# SilentStepStick-TMC2100_v12_5V.net
KiCad netlist of a schematic drawn in EAGLE
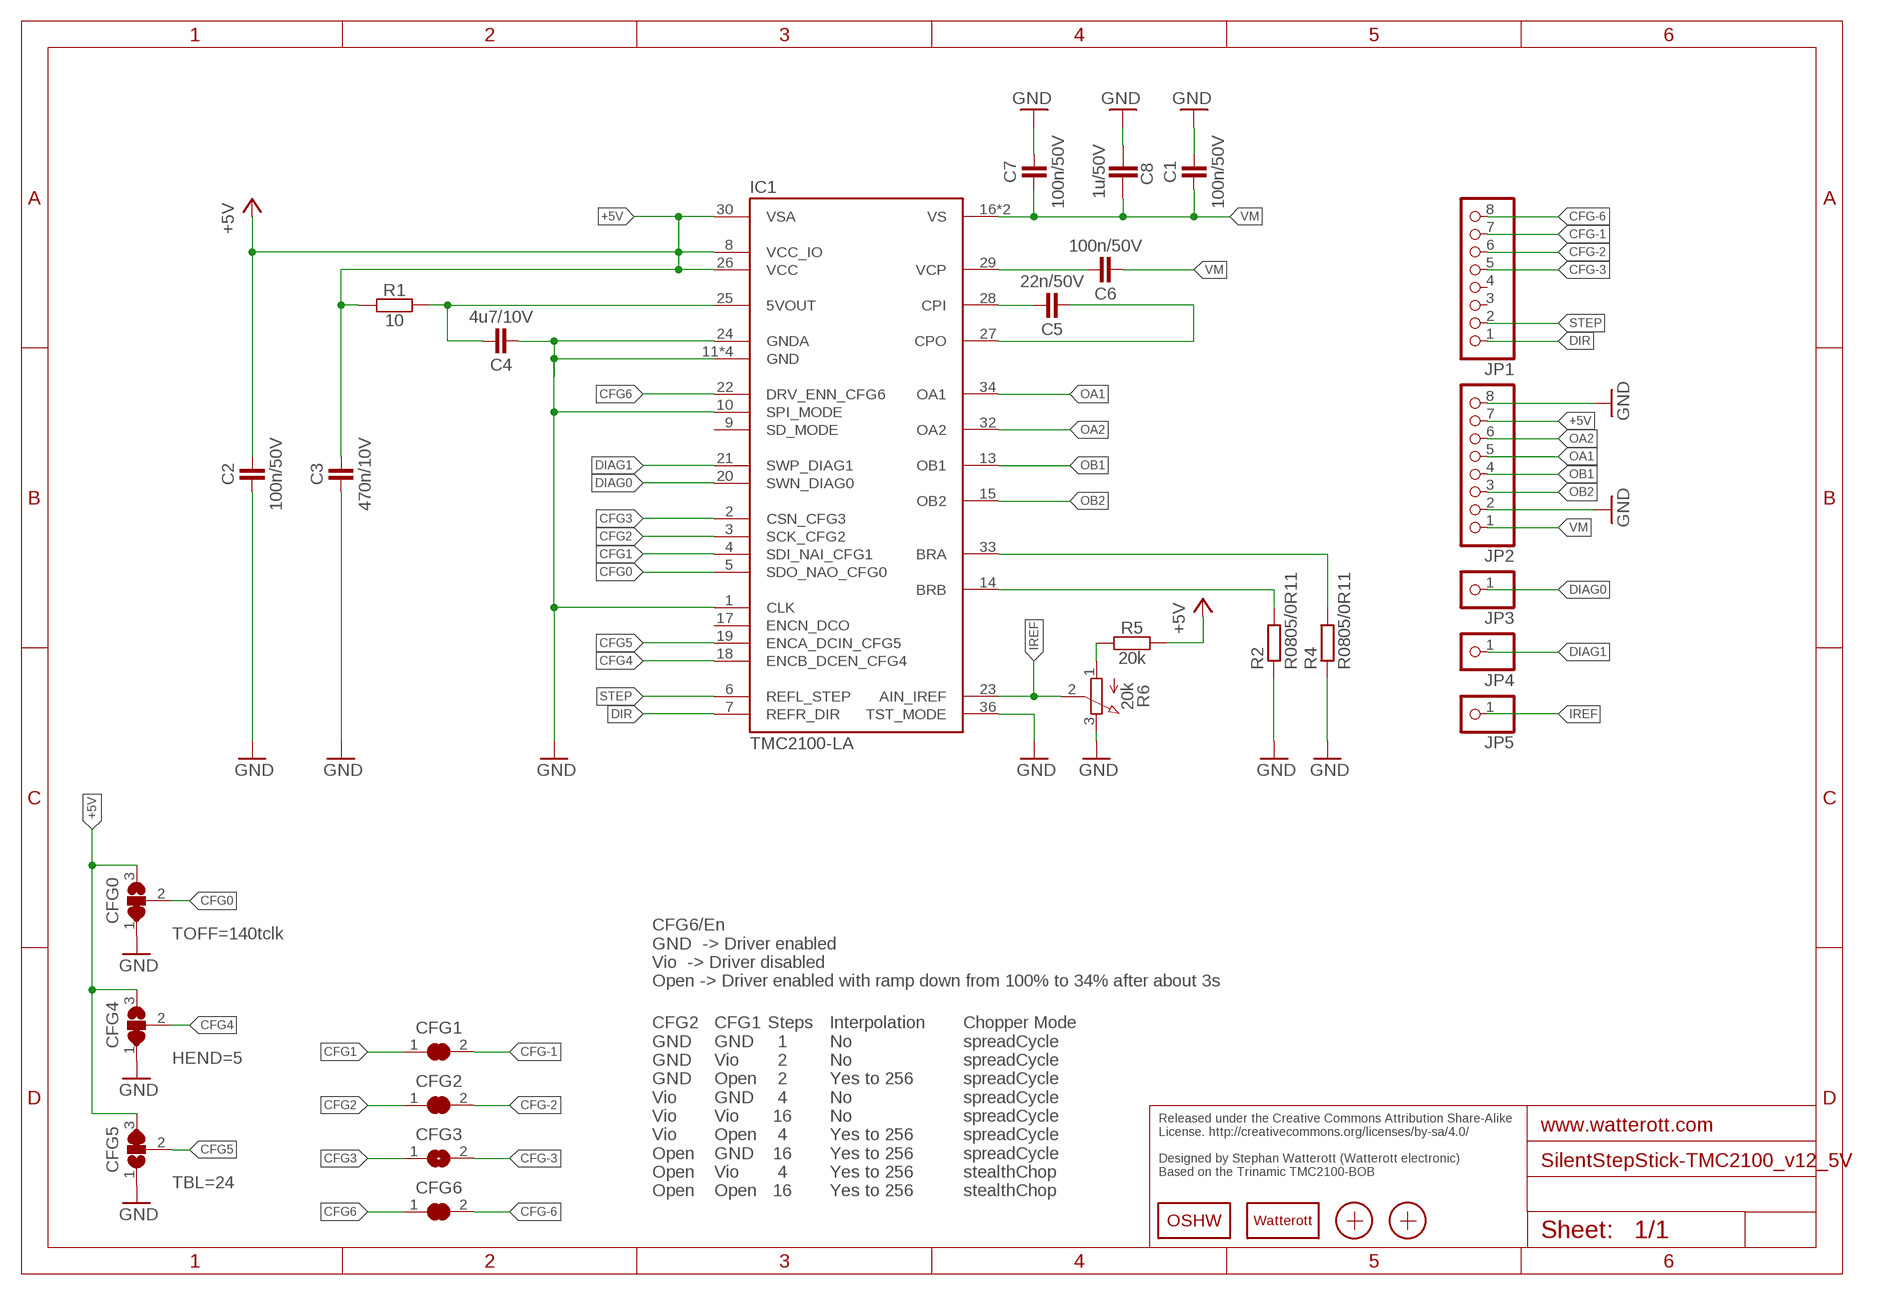
[diagram p0: schematic, sheet 1]

(export (version "E")
  (design (tool "Eeschema 10.0.6"))
  (components
    (comp (ref "C1")
      (value "100n/50V")
      (footprint "eagle-import:C0402")
      (libsource (lib "eagle-import") (part "CAPACITOR-0402"))
    )
    (comp (ref "C2")
      (value "100n/50V")
      (footprint "eagle-import:C0402")
      (libsource (lib "eagle-import") (part "CAPACITOR-0402"))
    )
    (comp (ref "C3")
      (value "470n/10V")
      (footprint "eagle-import:C0402")
      (libsource (lib "eagle-import") (part "CAPACITOR-0402"))
    )
    (comp (ref "C4")
      (value "4u7/10V")
      (footprint "eagle-import:C0402")
      (libsource (lib "eagle-import") (part "CAPACITOR-0402"))
    )
    (comp (ref "C5")
      (value "22n/50V")
      (footprint "eagle-import:C0402")
      (libsource (lib "eagle-import") (part "CAPACITOR-0402"))
    )
    (comp (ref "C6")
      (value "100n/50V")
      (footprint "eagle-import:C0402")
      (libsource (lib "eagle-import") (part "CAPACITOR-0402"))
    )
    (comp (ref "C7")
      (value "100n/50V")
      (footprint "eagle-import:C0402")
      (libsource (lib "eagle-import") (part "CAPACITOR-0402"))
    )
    (comp (ref "C8")
      (value "1u/50V")
      (footprint "eagle-import:C0603")
      (libsource (lib "eagle-import") (part "C-EUC0603"))
    )
    (comp (ref "CFG0")
      (value "JUMPER3-0201")
      (footprint "eagle-import:JUMPER3-0201")
      (libsource (lib "eagle-import") (part "JUMPER3-0201"))
    )
    (comp (ref "CFG1")
      (value "JUMPER2-0201")
      (footprint "eagle-import:JUMPER2-0201")
      (libsource (lib "eagle-import") (part "JUMPER2-0201"))
    )
    (comp (ref "CFG2")
      (value "JUMPER2-0201")
      (footprint "eagle-import:JUMPER2-0201")
      (libsource (lib "eagle-import") (part "JUMPER2-0201"))
    )
    (comp (ref "CFG3")
      (value "JUMPER2-0201")
      (footprint "eagle-import:JUMPER2-0201")
      (libsource (lib "eagle-import") (part "JUMPER2-0201"))
    )
    (comp (ref "CFG4")
      (value "JUMPER3-0201")
      (footprint "eagle-import:JUMPER3-0201")
      (libsource (lib "eagle-import") (part "JUMPER3-0201"))
    )
    (comp (ref "CFG5")
      (value "JUMPER3-0201")
      (footprint "eagle-import:JUMPER3-0201")
      (libsource (lib "eagle-import") (part "JUMPER3-0201"))
    )
    (comp (ref "CFG6")
      (value "JUMPER2-0201")
      (footprint "eagle-import:JUMPER2-0201")
      (libsource (lib "eagle-import") (part "JUMPER2-0201"))
    )
    (comp (ref "IC1")
      (value "TMC2100-LA")
      (footprint "eagle-import:QFN36-PAD")
      (libsource (lib "eagle-import") (part "TMC21X0-LA"))
    )
    (comp (ref "JP1")
      (value "PINHD-1X08_2.54-S")
      (footprint "eagle-import:1X08-S")
      (libsource (lib "eagle-import") (part "PINHD-1X08_2.54-S"))
    )
    (comp (ref "JP2")
      (value "PINHD-1X08_2.54-S")
      (footprint "eagle-import:1X08-S")
      (libsource (lib "eagle-import") (part "PINHD-1X08_2.54-S"))
    )
    (comp (ref "JP3")
      (value "PINHD-1X1")
      (footprint "eagle-import:1X01")
      (libsource (lib "eagle-import") (part "PINHD-1X1"))
    )
    (comp (ref "JP4")
      (value "PINHD-1X1")
      (footprint "eagle-import:1X01")
      (libsource (lib "eagle-import") (part "PINHD-1X1"))
    )
    (comp (ref "JP5")
      (value "PINHD-1X1")
      (footprint "eagle-import:1X01")
      (libsource (lib "eagle-import") (part "PINHD-1X1"))
    )
    (comp (ref "LOGO1")
      (value "OSHW_LOGOX0070")
      (footprint "eagle-import:OSHW_6X70")
      (libsource (lib "eagle-import") (part "OSHW_LOGOX0070"))
    )
    (comp (ref "LOGO2")
      (value "LOGO-S_PLACE_M")
      (footprint "eagle-import:SPARK_TPLACE_M")
      (libsource (lib "eagle-import") (part "LOGO-S_PLACE_M"))
    )
    (comp (ref "R1")
      (value "10")
      (footprint "eagle-import:C0402")
      (libsource (lib "eagle-import") (part "RESISTOR-0402"))
    )
    (comp (ref "R2")
      (value "R0805/0R11")
      (footprint "eagle-import:M0805")
      (libsource (lib "eagle-import") (part "R-EU_M0805"))
    )
    (comp (ref "R4")
      (value "R0805/0R11")
      (footprint "eagle-import:M0805")
      (libsource (lib "eagle-import") (part "R-EU_M0805"))
    )
    (comp (ref "R5")
      (value "20k")
      (footprint "eagle-import:C0402")
      (libsource (lib "eagle-import") (part "RESISTOR-0402"))
    )
    (comp (ref "R6")
      (value "20k")
      (footprint "eagle-import:POT_EVM3R")
      (libsource (lib "eagle-import") (part "POTEVM3R"))
    )
    (comp (ref "X1")
      (value "PASSER-07")
      (footprint "eagle-import:PASSER_07MM")
      (libsource (lib "eagle-import") (part "PASSER-07"))
    )
    (comp (ref "X2")
      (value "PASSER-07")
      (footprint "eagle-import:PASSER_07MM")
      (libsource (lib "eagle-import") (part "PASSER-07"))
    )
  )
  (nets
    (net (code "1") (name "+5V") (class "Default")
      (node (ref "C2") (pin "2") (pinfunction "2_2") (pintype "passive"))
      (node (ref "C3") (pin "2") (pinfunction "2_2") (pintype "passive"))
      (node (ref "CFG0") (pin "3") (pinfunction "3_3") (pintype "passive"))
      (node (ref "CFG4") (pin "3") (pinfunction "3_3") (pintype "passive"))
      (node (ref "CFG5") (pin "3") (pinfunction "3_3") (pintype "passive"))
      (node (ref "IC1") (pin "26") (pinfunction "VCC_26") (pintype "power_in"))
      (node (ref "IC1") (pin "30") (pinfunction "VSA_30") (pintype "power_in"))
      (node (ref "IC1") (pin "8") (pinfunction "VCC_IO_8") (pintype "power_in"))
      (node (ref "JP2") (pin "7") (pinfunction "7_7") (pintype "passive"))
      (node (ref "R1") (pin "1") (pinfunction "1_1") (pintype "passive"))
      (node (ref "R5") (pin "2") (pinfunction "2_2") (pintype "passive"))
    )
    (net (code "2") (name "CFG-1") (class "Default")
      (node (ref "CFG1") (pin "2") (pinfunction "2_2") (pintype "passive"))
      (node (ref "JP1") (pin "7") (pinfunction "7_7") (pintype "passive"))
    )
    (net (code "3") (name "CFG-2") (class "Default")
      (node (ref "CFG2") (pin "2") (pinfunction "2_2") (pintype "passive"))
      (node (ref "JP1") (pin "6") (pinfunction "6_6") (pintype "passive"))
    )
    (net (code "4") (name "CFG-3") (class "Default")
      (node (ref "CFG3") (pin "2") (pinfunction "2_2") (pintype "passive"))
      (node (ref "JP1") (pin "5") (pinfunction "5_5") (pintype "passive"))
    )
    (net (code "5") (name "CFG-6") (class "Default")
      (node (ref "CFG6") (pin "2") (pinfunction "2_2") (pintype "passive"))
      (node (ref "JP1") (pin "8") (pinfunction "8_8") (pintype "passive"))
    )
    (net (code "6") (name "CFG0") (class "Default")
      (node (ref "CFG0") (pin "2") (pinfunction "2_2") (pintype "passive"))
      (node (ref "IC1") (pin "5") (pinfunction "SDO_NAO_CFG0_5") (pintype "bidirectional"))
    )
    (net (code "7") (name "CFG1") (class "Default")
      (node (ref "CFG1") (pin "1") (pinfunction "1_1") (pintype "passive"))
      (node (ref "IC1") (pin "4") (pinfunction "SDI_NAI_CFG1_4") (pintype "bidirectional"))
    )
    (net (code "8") (name "CFG2") (class "Default")
      (node (ref "CFG2") (pin "1") (pinfunction "1_1") (pintype "passive"))
      (node (ref "IC1") (pin "3") (pinfunction "SCK_CFG2_3") (pintype "bidirectional"))
    )
    (net (code "9") (name "CFG3") (class "Default")
      (node (ref "CFG3") (pin "1") (pinfunction "1_1") (pintype "passive"))
      (node (ref "IC1") (pin "2") (pinfunction "CSN_CFG3_2") (pintype "bidirectional"))
    )
    (net (code "10") (name "CFG4") (class "Default")
      (node (ref "CFG4") (pin "2") (pinfunction "2_2") (pintype "passive"))
      (node (ref "IC1") (pin "18") (pinfunction "ENCB_DCEN_CFG4_18") (pintype "bidirectional"))
    )
    (net (code "11") (name "CFG5") (class "Default")
      (node (ref "CFG5") (pin "2") (pinfunction "2_2") (pintype "passive"))
      (node (ref "IC1") (pin "19") (pinfunction "ENCA_DCIN_CFG5_19") (pintype "bidirectional"))
    )
    (net (code "12") (name "CFG6") (class "Default")
      (node (ref "CFG6") (pin "1") (pinfunction "1_1") (pintype "passive"))
      (node (ref "IC1") (pin "22") (pinfunction "DRV_ENN_CFG6_22") (pintype "bidirectional"))
    )
    (net (code "13") (name "DIAG0") (class "Default")
      (node (ref "IC1") (pin "20") (pinfunction "SWN_DIAG0_20") (pintype "bidirectional"))
      (node (ref "JP3") (pin "1") (pinfunction "1_1") (pintype "passive"))
    )
    (net (code "14") (name "DIAG1") (class "Default")
      (node (ref "IC1") (pin "21") (pinfunction "SWP_DIAG1_21") (pintype "bidirectional"))
      (node (ref "JP4") (pin "1") (pinfunction "1_1") (pintype "passive"))
    )
    (net (code "15") (name "DIR") (class "Default")
      (node (ref "IC1") (pin "7") (pinfunction "REFR_DIR_7") (pintype "bidirectional"))
      (node (ref "JP1") (pin "1") (pinfunction "1_1") (pintype "passive"))
    )
    (net (code "16") (name "GND") (class "Default")
      (node (ref "C1") (pin "2") (pinfunction "2_2") (pintype "passive"))
      (node (ref "C2") (pin "1") (pinfunction "1_1") (pintype "passive"))
      (node (ref "C3") (pin "1") (pinfunction "1_1") (pintype "passive"))
      (node (ref "C4") (pin "1") (pinfunction "1_1") (pintype "passive"))
      (node (ref "C7") (pin "2") (pinfunction "2_2") (pintype "passive"))
      (node (ref "C8") (pin "2") (pinfunction "2_2") (pintype "passive"))
      (node (ref "CFG0") (pin "1") (pinfunction "1_1") (pintype "passive"))
      (node (ref "CFG4") (pin "1") (pinfunction "1_1") (pintype "passive"))
      (node (ref "CFG5") (pin "1") (pinfunction "1_1") (pintype "passive"))
      (node (ref "IC1") (pin "1") (pinfunction "CLK_1") (pintype "bidirectional"))
      (node (ref "IC1") (pin "10") (pinfunction "SPI_MODE_10") (pintype "bidirectional"))
      (node (ref "IC1") (pin "11") (pinfunction "GND_11") (pintype "power_in"))
      (node (ref "IC1") (pin "12") (pinfunction "GND_12") (pintype "power_in"))
      (node (ref "IC1") (pin "24") (pinfunction "GNDA_24") (pintype "power_in"))
      (node (ref "IC1") (pin "35") (pinfunction "GND_35") (pintype "power_in"))
      (node (ref "IC1") (pin "36") (pinfunction "TST_MODE_36") (pintype "bidirectional"))
      (node (ref "IC1") (pin "TP") (pinfunction "GND_TP") (pintype "power_in"))
      (node (ref "JP2") (pin "2") (pinfunction "2_2") (pintype "passive"))
      (node (ref "JP2") (pin "8") (pinfunction "8_8") (pintype "passive"))
      (node (ref "R2") (pin "1") (pinfunction "1_1") (pintype "passive"))
      (node (ref "R4") (pin "1") (pinfunction "1_1") (pintype "passive"))
      (node (ref "R6") (pin "3") (pinfunction "E_3") (pintype "passive"))
    )
    (net (code "17") (name "IREF") (class "Default")
      (node (ref "IC1") (pin "23") (pinfunction "AIN_IREF_23") (pintype "passive"))
      (node (ref "JP5") (pin "1") (pinfunction "1_1") (pintype "passive"))
      (node (ref "R6") (pin "2") (pinfunction "S_2") (pintype "passive"))
    )
    (net (code "18") (name "Net-(IC1-5VOUT)") (class "Default")
      (node (ref "C4") (pin "2") (pinfunction "2_2") (pintype "passive"))
      (node (ref "IC1") (pin "25") (pinfunction "5VOUT_25") (pintype "power_in"))
      (node (ref "R1") (pin "2") (pinfunction "2_2") (pintype "passive"))
    )
    (net (code "19") (name "Net-(IC1-BRA)") (class "Default")
      (node (ref "IC1") (pin "33") (pinfunction "BRA_33") (pintype "output"))
      (node (ref "R4") (pin "2") (pinfunction "2_2") (pintype "passive"))
    )
    (net (code "20") (name "Net-(IC1-BRB)") (class "Default")
      (node (ref "IC1") (pin "14") (pinfunction "BRB_14") (pintype "output"))
      (node (ref "R2") (pin "2") (pinfunction "2_2") (pintype "passive"))
    )
    (net (code "21") (name "Net-(IC1-CPI)") (class "Default")
      (node (ref "C5") (pin "2") (pinfunction "2_2") (pintype "passive"))
      (node (ref "IC1") (pin "28") (pinfunction "CPI_28") (pintype "passive"))
    )
    (net (code "22") (name "Net-(IC1-CPO)") (class "Default")
      (node (ref "C5") (pin "1") (pinfunction "1_1") (pintype "passive"))
      (node (ref "IC1") (pin "27") (pinfunction "CPO_27") (pintype "passive"))
    )
    (net (code "23") (name "Net-(IC1-VCP)") (class "Default")
      (node (ref "C6") (pin "2") (pinfunction "2_2") (pintype "passive"))
      (node (ref "IC1") (pin "29") (pinfunction "VCP_29") (pintype "passive"))
    )
    (net (code "24") (name "Net-(R6-A)") (class "Default")
      (node (ref "R5") (pin "1") (pinfunction "1_1") (pintype "passive"))
      (node (ref "R6") (pin "1") (pinfunction "A_1") (pintype "passive"))
    )
    (net (code "25") (name "OA1") (class "Default")
      (node (ref "IC1") (pin "34") (pinfunction "OA1_34") (pintype "output"))
      (node (ref "JP2") (pin "5") (pinfunction "5_5") (pintype "passive"))
    )
    (net (code "26") (name "OA2") (class "Default")
      (node (ref "IC1") (pin "32") (pinfunction "OA2_32") (pintype "output"))
      (node (ref "JP2") (pin "6") (pinfunction "6_6") (pintype "passive"))
    )
    (net (code "27") (name "OB1") (class "Default")
      (node (ref "IC1") (pin "13") (pinfunction "OB1_13") (pintype "output"))
      (node (ref "JP2") (pin "4") (pinfunction "4_4") (pintype "passive"))
    )
    (net (code "28") (name "OB2") (class "Default")
      (node (ref "IC1") (pin "15") (pinfunction "OB2_15") (pintype "output"))
      (node (ref "JP2") (pin "3") (pinfunction "3_3") (pintype "passive"))
    )
    (net (code "29") (name "STEP") (class "Default")
      (node (ref "IC1") (pin "6") (pinfunction "REFL_STEP_6") (pintype "bidirectional"))
      (node (ref "JP1") (pin "2") (pinfunction "2_2") (pintype "passive"))
    )
    (net (code "30") (name "VM") (class "Default")
      (node (ref "C1") (pin "1") (pinfunction "1_1") (pintype "passive"))
      (node (ref "C6") (pin "1") (pinfunction "1_1") (pintype "passive"))
      (node (ref "C7") (pin "1") (pinfunction "1_1") (pintype "passive"))
      (node (ref "C8") (pin "1") (pinfunction "1_1") (pintype "passive"))
      (node (ref "IC1") (pin "16") (pinfunction "VS_16") (pintype "power_in"))
      (node (ref "IC1") (pin "31") (pinfunction "VS_31") (pintype "power_in"))
      (node (ref "JP2") (pin "1") (pinfunction "1_1") (pintype "passive"))
    )
    (net (code "31") (name "unconnected-(IC1-ENCN_DCO-Pad17)") (class "Default")
      (node (ref "IC1") (pin "17") (pinfunction "ENCN_DCO_17") (pintype "bidirectional"))
    )
    (net (code "32") (name "unconnected-(IC1-SD_MODE-Pad9)") (class "Default")
      (node (ref "IC1") (pin "9") (pinfunction "SD_MODE_9") (pintype "bidirectional"))
    )
    (net (code "33") (name "unconnected-(JP1-Pad3)") (class "Default")
      (node (ref "JP1") (pin "3") (pinfunction "3_3") (pintype "passive"))
    )
    (net (code "34") (name "unconnected-(JP1-Pad4)") (class "Default")
      (node (ref "JP1") (pin "4") (pinfunction "4_4") (pintype "passive"))
    )
  )
)
